# DC075B_USB.net
KiCad netlist of a schematic drawn in Altium Designer
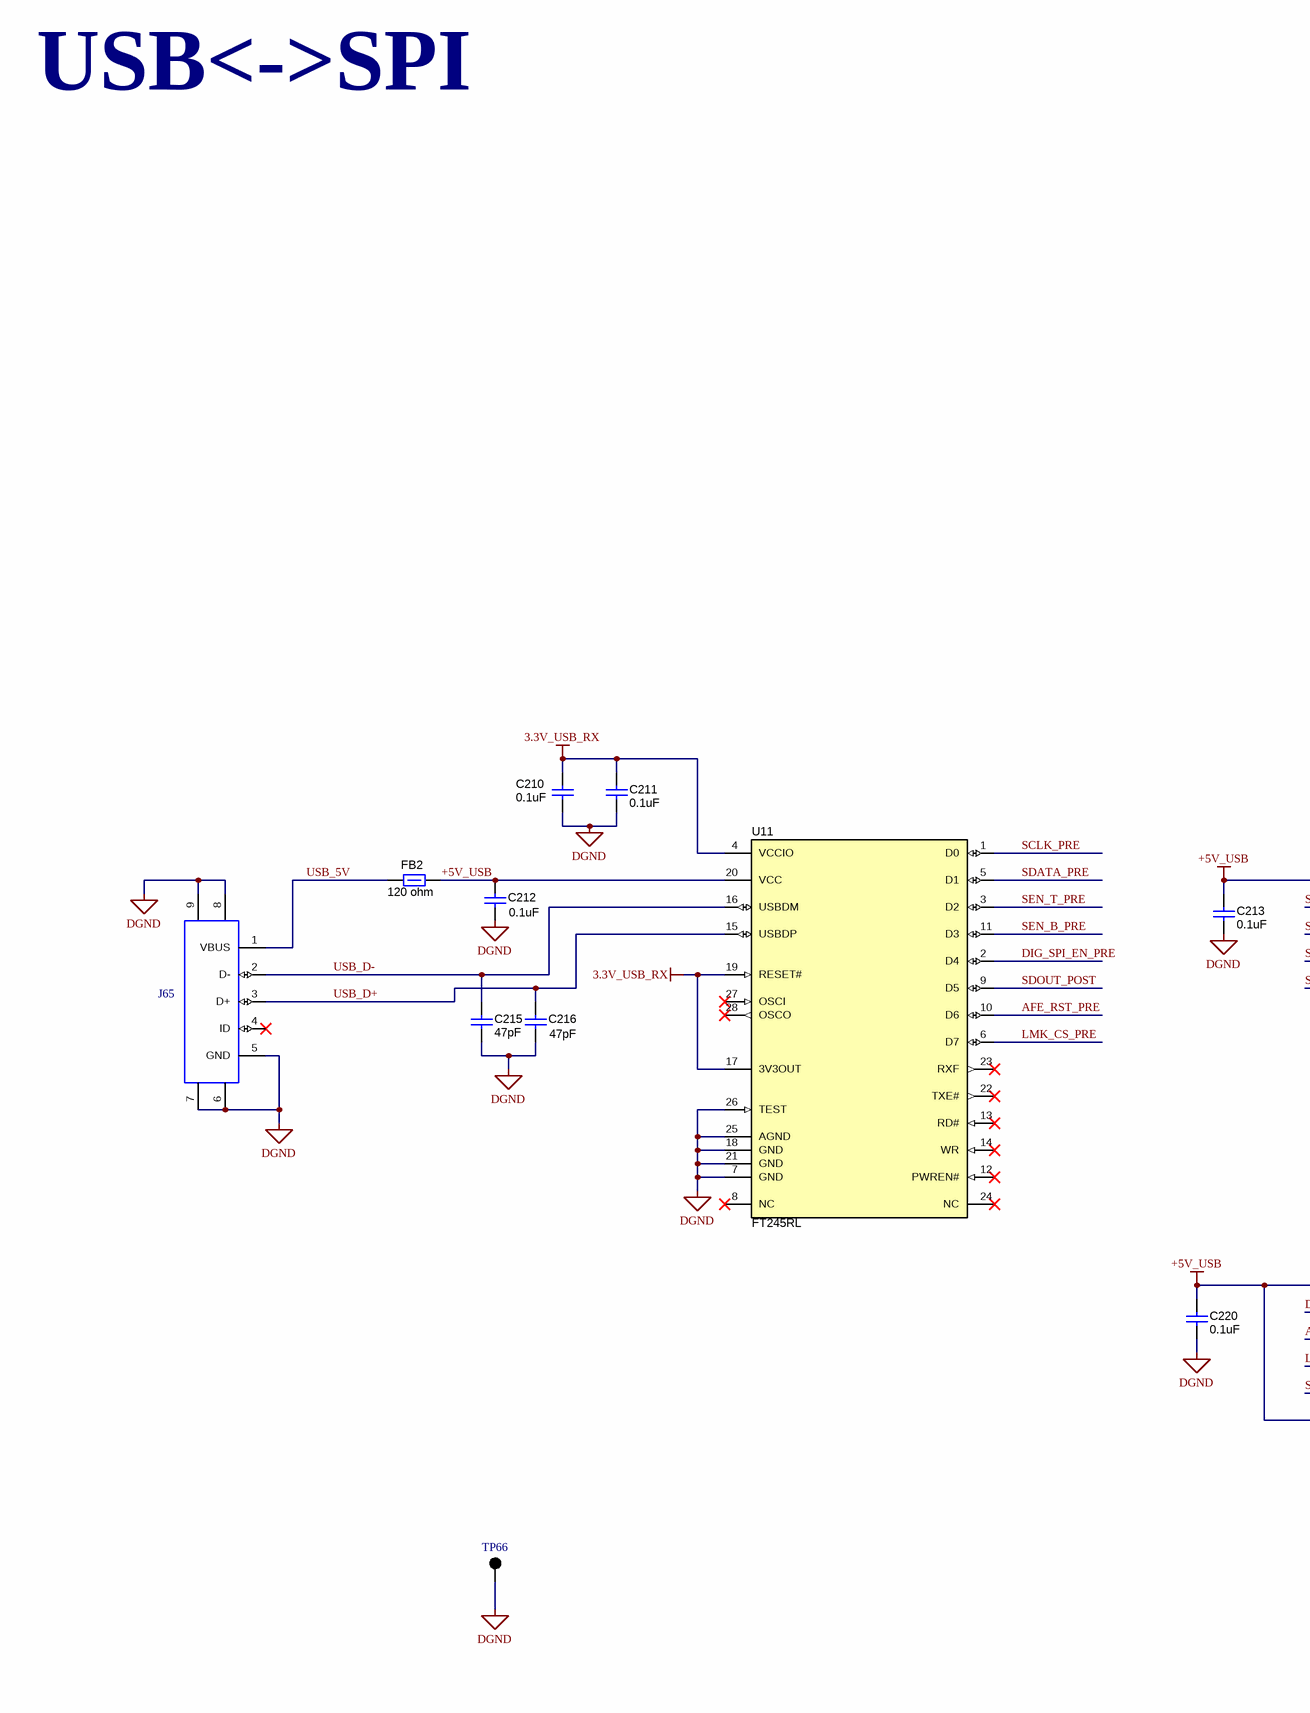
[diagram p0: DC075B_USB.SchDoc, left]
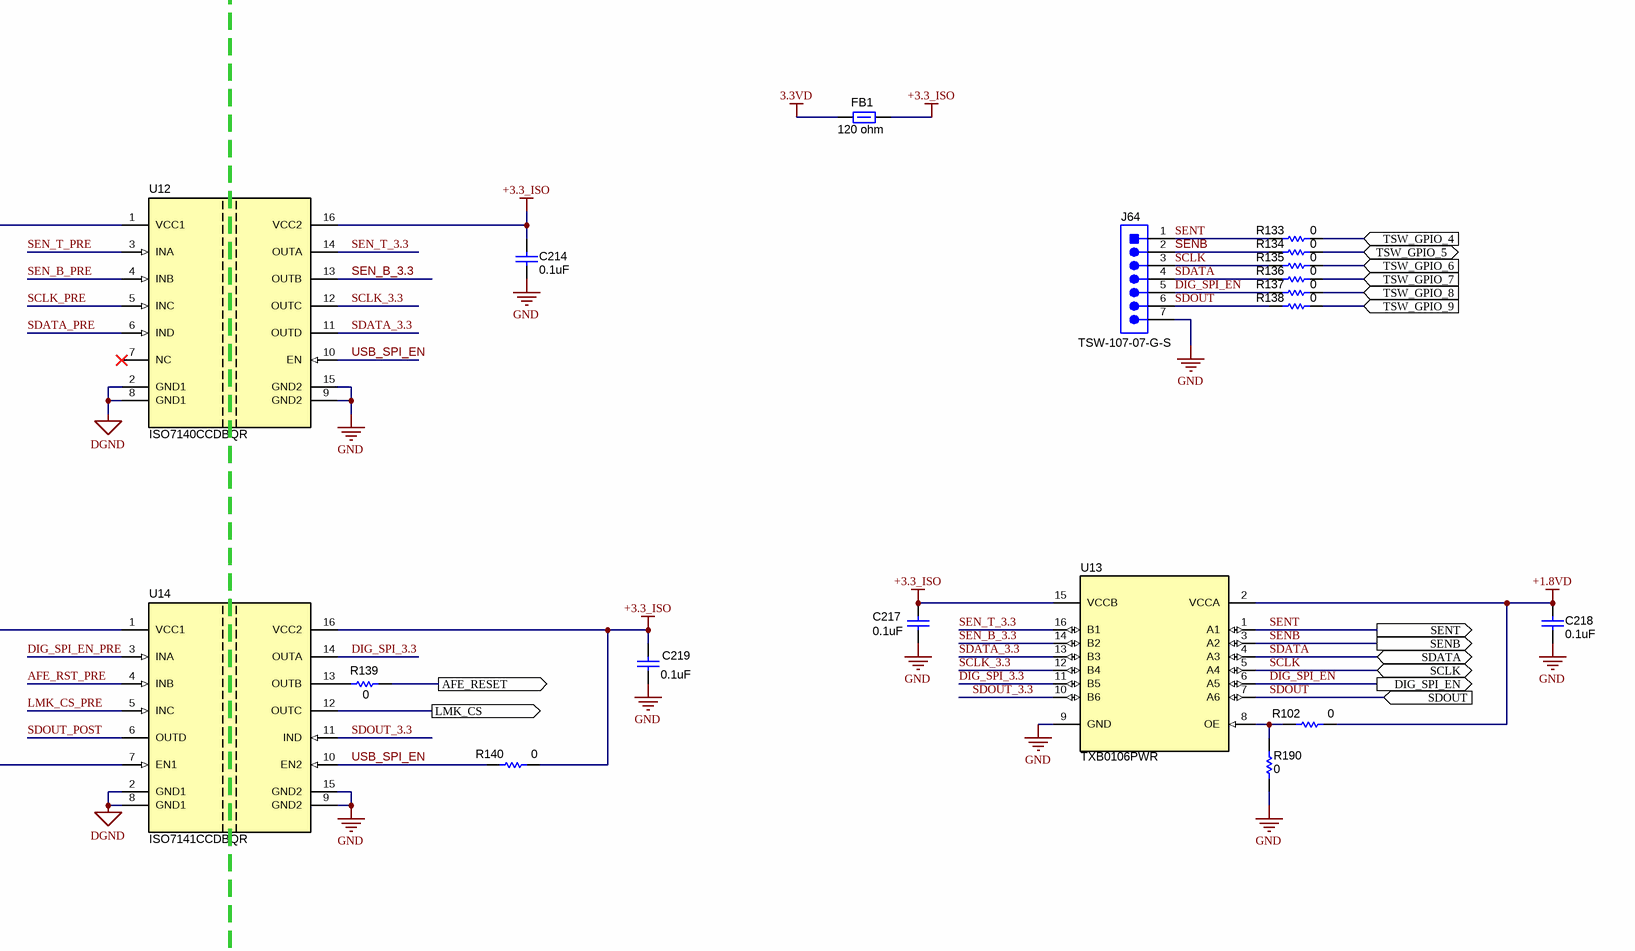
[diagram p1: DC075B_USB.SchDoc, right]

(export (version "E")
  (design (tool "Eeschema 10.0.6"))
  (components
    (comp (ref "C210")
      (value "0.1uF")
      (footprint "0402")
      (description "CAP, CERM, 0.1 uF, 16 V, +/- 10%, X7R, 0402")
      (fields
        (field (name "PARTNUMBER") "GRM155R71C104KA88D")
        (field (name "MANUFACTURER") "MuRata")
        (field (name "PUBLISHER") "Texas Instruments")
      )
      (libsource (lib "Altium Vault - TI") (part "Capacitor"))
    )
    (comp (ref "C211")
      (value "0.1uF")
      (footprint "0402")
      (description "CAP, CERM, 0.1 uF, 16 V, +/- 10%, X7R, 0402")
      (fields
        (field (name "PARTNUMBER") "GRM155R71C104KA88D")
        (field (name "MANUFACTURER") "MuRata")
        (field (name "PUBLISHER") "Texas Instruments")
      )
      (libsource (lib "Altium Vault - TI") (part "Capacitor"))
    )
    (comp (ref "C212")
      (value "0.1uF")
      (footprint "0402")
      (description "CAP, CERM, 0.1 uF, 16 V, +/- 10%, X7R, 0402")
      (fields
        (field (name "PARTNUMBER") "GRM155R71C104KA88D")
        (field (name "MANUFACTURER") "MuRata")
        (field (name "PUBLISHER") "Texas Instruments")
      )
      (libsource (lib "Altium Vault - TI") (part "Capacitor"))
    )
    (comp (ref "C213")
      (value "0.1uF")
      (footprint "0402")
      (description "CAP, CERM, 0.1 uF, 16 V, +/- 10%, X7R, 0402")
      (fields
        (field (name "PARTNUMBER") "GRM155R71C104KA88D")
        (field (name "MANUFACTURER") "MuRata")
        (field (name "PUBLISHER") "Texas Instruments")
      )
      (libsource (lib "Altium Vault - TI") (part "Capacitor"))
    )
    (comp (ref "C214")
      (value "0.1uF")
      (footprint "0402")
      (description "CAP, CERM, 0.1 uF, 16 V, +/- 10%, X7R, 0402")
      (fields
        (field (name "PARTNUMBER") "GRM155R71C104KA88D")
        (field (name "MANUFACTURER") "MuRata")
        (field (name "PUBLISHER") "Texas Instruments")
      )
      (libsource (lib "Altium Vault - TI") (part "Capacitor"))
    )
    (comp (ref "C215")
      (value "47pF")
      (footprint "0402")
      (description "CAP, CERM, 47 pF, 50 V, +/- 1%, C0G/NP0, 0402")
      (fields
        (field (name "PARTNUMBER") "GRM1555C1H470FA01D")
        (field (name "MANUFACTURER") "MuRata")
        (field (name "PUBLISHER") "Texas Instruments")
      )
      (libsource (lib "Altium Vault - TI") (part "Capacitor"))
    )
    (comp (ref "C216")
      (value "47pF")
      (footprint "0402")
      (description "CAP, CERM, 47 pF, 50 V, +/- 1%, C0G/NP0, 0402")
      (fields
        (field (name "PARTNUMBER") "GRM1555C1H470FA01D")
        (field (name "MANUFACTURER") "MuRata")
        (field (name "PUBLISHER") "Texas Instruments")
      )
      (libsource (lib "Altium Vault - TI") (part "Capacitor"))
    )
    (comp (ref "C217")
      (value "0.1uF")
      (footprint "0402")
      (description "CAP, CERM, 0.1 uF, 16 V, +/- 10%, X7R, 0402")
      (fields
        (field (name "PARTNUMBER") "GRM155R71C104KA88D")
        (field (name "MANUFACTURER") "MuRata")
        (field (name "PUBLISHER") "Texas Instruments")
      )
      (libsource (lib "Altium Vault - TI") (part "Capacitor"))
    )
    (comp (ref "C218")
      (value "0.1uF")
      (footprint "0402")
      (description "CAP, CERM, 0.1 uF, 16 V, +/- 10%, X7R, 0402")
      (fields
        (field (name "PARTNUMBER") "GRM155R71C104KA88D")
        (field (name "MANUFACTURER") "MuRata")
        (field (name "PUBLISHER") "Texas Instruments")
      )
      (libsource (lib "Altium Vault - TI") (part "Capacitor"))
    )
    (comp (ref "C219")
      (value "0.1uF")
      (footprint "0402")
      (description "CAP, CERM, 0.1 uF, 16 V, +/- 10%, X7R, 0402")
      (fields
        (field (name "PARTNUMBER") "GRM155R71C104KA88D")
        (field (name "MANUFACTURER") "MuRata")
        (field (name "PUBLISHER") "Texas Instruments")
      )
      (libsource (lib "Altium Vault - TI") (part "Capacitor"))
    )
    (comp (ref "C220")
      (value "0.1uF")
      (footprint "0402")
      (description "CAP, CERM, 0.1 uF, 16 V, +/- 10%, X7R, 0402")
      (fields
        (field (name "PARTNUMBER") "GRM155R71C104KA88D")
        (field (name "MANUFACTURER") "MuRata")
        (field (name "PUBLISHER") "Texas Instruments")
      )
      (libsource (lib "Altium Vault - TI") (part "Capacitor"))
    )
    (comp (ref "FB1")
      (value "120 ohm")
      (footprint "0805")
      (description "Ferrite Bead, 120 ohm @ 100 MHz, 0.8 A, 0805")
      (fields
        (field (name "MANUFACTURER") "MuRata")
        (field (name "PARTNUMBER") "BLM21AG121SN1D")
        (field (name "PUBLISHER") "Texas Instruments")
      )
      (libsource (lib "Altium Vault - TI") (part "Ferrite_Bead"))
    )
    (comp (ref "FB2")
      (value "120 ohm")
      (footprint "0805")
      (description "Ferrite Bead, 120 ohm @ 100 MHz, 0.8 A, 0805")
      (fields
        (field (name "MANUFACTURER") "MuRata")
        (field (name "PARTNUMBER") "BLM21AG121SN1D")
        (field (name "PUBLISHER") "Texas Instruments")
      )
      (libsource (lib "Altium Vault - TI") (part "Ferrite_Bead"))
    )
    (comp (ref "J64")
      (value "TSW-107-07-G-S")
      (footprint "TSW-107-07-G-S")
      (description "Header, 100mil, 7x1, Gold, TH")
      (fields (field (name "MANUFACTURER") "Samtec") (field (name "PUBLISHER") "Texas Instruments"))
      (libsource (lib "Altium Vault - TI") (part "Header_7x1"))
    )
    (comp (ref "J65")
      (value "67803-8020")
      (footprint "Molex_67803-8020")
      (description "Connector, Receptacle, USB - mini AB, R/A, SMD")
      (fields (field (name "MANUFACTURER") "Molex") (field (name "PUBLISHER") "Texas Instruments"))
      (libsource (lib "Altium Vault - TI") (part "CONN_USB_MINI-AB_4Shld"))
    )
    (comp (ref "R102")
      (value "0")
      (footprint "0402")
      (description "RES, 0, 5%, 0.063 W, AEC-Q200 Grade 0, 0402")
      (fields (field (name "MANUFACTURER") "Vishay-Dale") (field (name "PARTNUMBER") "CRCW04020000Z0ED"))
      (libsource (lib "Altium Vault - TI") (part "Resistor"))
    )
    (comp (ref "R133")
      (value "0")
      (footprint "0402")
      (description "RES, 0, 5%, 0.063 W, AEC-Q200 Grade 0, 0402")
      (fields (field (name "MANUFACTURER") "Vishay-Dale") (field (name "PARTNUMBER") "CRCW04020000Z0ED"))
      (libsource (lib "Altium Vault - TI") (part "Resistor"))
    )
    (comp (ref "R134")
      (value "0")
      (footprint "0402")
      (description "RES, 0, 5%, 0.063 W, AEC-Q200 Grade 0, 0402")
      (fields (field (name "MANUFACTURER") "Vishay-Dale") (field (name "PARTNUMBER") "CRCW04020000Z0ED"))
      (libsource (lib "Altium Vault - TI") (part "Resistor"))
    )
    (comp (ref "R135")
      (value "0")
      (footprint "0402")
      (description "RES, 0, 5%, 0.063 W, AEC-Q200 Grade 0, 0402")
      (fields (field (name "MANUFACTURER") "Vishay-Dale") (field (name "PARTNUMBER") "CRCW04020000Z0ED"))
      (libsource (lib "Altium Vault - TI") (part "Resistor"))
    )
    (comp (ref "R136")
      (value "0")
      (footprint "0402")
      (description "RES, 0, 5%, 0.063 W, AEC-Q200 Grade 0, 0402")
      (fields (field (name "MANUFACTURER") "Vishay-Dale") (field (name "PARTNUMBER") "CRCW04020000Z0ED"))
      (libsource (lib "Altium Vault - TI") (part "Resistor"))
    )
    (comp (ref "R137")
      (value "0")
      (footprint "0402")
      (description "RES, 0, 5%, 0.063 W, AEC-Q200 Grade 0, 0402")
      (fields (field (name "MANUFACTURER") "Vishay-Dale") (field (name "PARTNUMBER") "CRCW04020000Z0ED"))
      (libsource (lib "Altium Vault - TI") (part "Resistor"))
    )
    (comp (ref "R138")
      (value "0")
      (footprint "0402")
      (description "RES, 0, 5%, 0.063 W, AEC-Q200 Grade 0, 0402")
      (fields (field (name "MANUFACTURER") "Vishay-Dale") (field (name "PARTNUMBER") "CRCW04020000Z0ED"))
      (libsource (lib "Altium Vault - TI") (part "Resistor"))
    )
    (comp (ref "R139")
      (value "0")
      (footprint "0402")
      (description "RES, 0, 5%, 0.063 W, AEC-Q200 Grade 0, 0402")
      (fields (field (name "MANUFACTURER") "Vishay-Dale") (field (name "PARTNUMBER") "CRCW04020000Z0ED"))
      (libsource (lib "Altium Vault - TI") (part "Resistor"))
    )
    (comp (ref "R140")
      (value "0")
      (footprint "0402")
      (description "RES, 0, 5%, 0.063 W, AEC-Q200 Grade 0, 0402")
      (fields (field (name "MANUFACTURER") "Vishay-Dale") (field (name "PARTNUMBER") "CRCW04020000Z0ED"))
      (libsource (lib "Altium Vault - TI") (part "Resistor"))
    )
    (comp (ref "R190")
      (value "0")
      (footprint "0402")
      (description "RES, 0, 5%, 0.063 W, AEC-Q200 Grade 0, 0402")
      (fields (field (name "MANUFACTURER") "Vishay-Dale") (field (name "PARTNUMBER") "CRCW04020000Z0ED"))
      (libsource (lib "Altium Vault - TI") (part "Resistor"))
    )
    (comp (ref "TP66")
      (value "5001")
      (footprint "Keystone5001")
      (description "Test Point, Miniature, Black, TH")
      (fields (field (name "MANUFACTURER") "Keystone") (field (name "PUBLISHER") "Texas Instruments"))
      (libsource (lib "Altium Vault - TI") (part "5001"))
    )
    (comp (ref "U11")
      (value "FT245RL")
      (footprint "SSOP28_N")
      (description "USB FIFO IC, 28SSOP")
      (fields (field (name "MANUFACTURER") "FTDI") (field (name "PUBLISHER") "Texas Instruments"))
      (libsource (lib "Altium Vault - TI") (part "FT245RL"))
    )
    (comp (ref "U12")
      (value "ISO7140CCDBQR")
      (footprint "DBQ0016A_N")
      (fields
        (field (name "ALTERNATE PARTNUMBER") "ISO7140CCDBQ")
        (field (name "MANUFACTURER") "Texas Instruments")
        (field (name "PUBLISHER") "Texas Instruments")
      )
      (libsource (lib "Altium Vault - TI") (part "ISO7140"))
    )
    (comp (ref "U13")
      (value "TXB0106PWR")
      (footprint "PW0016A_N")
      (fields
        (field (name "MANUFACTURER") "Texas Instruments")
        (field (name "PUBLISHER") "Texas Instruments")
      )
      (libsource (lib "Altium Vault - TI") (part "TXB0106PW"))
    )
    (comp (ref "U14")
      (value "ISO7141CCDBQR")
      (footprint "DBQ0016A_N")
      (fields
        (field (name "ALTERNATE PARTNUMBER") "ISO7141CCDBQ")
        (field (name "MANUFACTURER") "Texas Instruments")
        (field (name "PUBLISHER") "Texas Instruments")
      )
      (libsource (lib "Altium Vault - TI") (part "ISO7141"))
    )
  )
  (nets
    (net (code "1") (name "+1.8VD") (class "Default")
      (node (ref "C218") (pin "2") (pinfunction "2_2") (pintype "passive"))
      (node (ref "R102") (pin "1") (pinfunction "1_1") (pintype "passive"))
      (node (ref "U13") (pin "2") (pinfunction "VCCA_2") (pintype "power_in"))
    )
    (net (code "2") (name "+3.3_ISO") (class "Default")
      (node (ref "C214") (pin "2") (pinfunction "2_2") (pintype "passive"))
      (node (ref "C217") (pin "2") (pinfunction "2_2") (pintype "passive"))
      (node (ref "C219") (pin "2") (pinfunction "2_2") (pintype "passive"))
      (node (ref "FB1") (pin "1") (pinfunction "1_1") (pintype "passive"))
      (node (ref "R140") (pin "1") (pinfunction "1_1") (pintype "passive"))
      (node (ref "U12") (pin "16") (pinfunction "VCC2_16") (pintype "power_in"))
      (node (ref "U13") (pin "15") (pinfunction "VCCB_15") (pintype "power_in"))
      (node (ref "U14") (pin "16") (pinfunction "VCC2_16") (pintype "power_in"))
    )
    (net (code "3") (name "+5V_USB") (class "Default")
      (node (ref "C212") (pin "1") (pinfunction "1_1") (pintype "passive"))
      (node (ref "C213") (pin "1") (pinfunction "1_1") (pintype "passive"))
      (node (ref "C220") (pin "1") (pinfunction "1_1") (pintype "passive"))
      (node (ref "FB2") (pin "1") (pinfunction "1_1") (pintype "passive"))
      (node (ref "U11") (pin "20") (pinfunction "VCC_20") (pintype "power_in"))
      (node (ref "U12") (pin "1") (pinfunction "VCC1_1") (pintype "power_in"))
      (node (ref "U14") (pin "1") (pinfunction "VCC1_1") (pintype "power_in"))
      (node (ref "U14") (pin "7") (pinfunction "EN1_7") (pintype "input"))
    )
    (net (code "4") (name "/AFE_RESET") (class "Default")
      (node (ref "R139") (pin "1") (pinfunction "1_1") (pintype "passive"))
    )
    (net (code "5") (name "/AFE_RST_PRE") (class "Default")
      (node (ref "U11") (pin "10") (pinfunction "D6_10") (pintype "bidirectional"))
      (node (ref "U14") (pin "4") (pinfunction "INB_4") (pintype "input"))
    )
    (net (code "6") (name "/DIG_SPI_3.3") (class "Default")
      (node (ref "U13") (pin "11") (pinfunction "B5_11") (pintype "bidirectional"))
      (node (ref "U14") (pin "14") (pinfunction "OUTA_14") (pintype "tri_state"))
    )
    (net (code "7") (name "/DIG_SPI_EN") (class "Default")
      (node (ref "J64") (pin "5") (pinfunction "5_5") (pintype "passive"))
      (node (ref "R137") (pin "2") (pinfunction "2_2") (pintype "passive"))
      (node (ref "U13") (pin "6") (pinfunction "A5_6") (pintype "bidirectional"))
    )
    (net (code "8") (name "/DIG_SPI_EN_PRE") (class "Default")
      (node (ref "U11") (pin "2") (pinfunction "D4_2") (pintype "bidirectional"))
      (node (ref "U14") (pin "3") (pinfunction "INA_3") (pintype "input"))
    )
    (net (code "9") (name "/LMK_CS") (class "Default")
      (node (ref "U14") (pin "12") (pinfunction "OUTC_12") (pintype "tri_state"))
    )
    (net (code "10") (name "/LMK_CS_PRE") (class "Default")
      (node (ref "U11") (pin "6") (pinfunction "D7_6") (pintype "bidirectional"))
      (node (ref "U14") (pin "5") (pinfunction "INC_5") (pintype "input"))
    )
    (net (code "11") (name "/SCLK") (class "Default")
      (node (ref "J64") (pin "3") (pinfunction "3_3") (pintype "passive"))
      (node (ref "R135") (pin "2") (pinfunction "2_2") (pintype "passive"))
      (node (ref "U13") (pin "5") (pinfunction "A4_5") (pintype "bidirectional"))
    )
    (net (code "12") (name "/SCLK_3.3") (class "Default")
      (node (ref "U12") (pin "12") (pinfunction "OUTC_12") (pintype "tri_state"))
      (node (ref "U13") (pin "12") (pinfunction "B4_12") (pintype "bidirectional"))
    )
    (net (code "13") (name "/SCLK_PRE") (class "Default")
      (node (ref "U11") (pin "1") (pinfunction "D0_1") (pintype "bidirectional"))
      (node (ref "U12") (pin "5") (pinfunction "INC_5") (pintype "input"))
    )
    (net (code "14") (name "/SDATA") (class "Default")
      (node (ref "J64") (pin "4") (pinfunction "4_4") (pintype "passive"))
      (node (ref "R136") (pin "2") (pinfunction "2_2") (pintype "passive"))
      (node (ref "U13") (pin "4") (pinfunction "A3_4") (pintype "bidirectional"))
    )
    (net (code "15") (name "/SDATA_3.3") (class "Default")
      (node (ref "U12") (pin "11") (pinfunction "OUTD_11") (pintype "tri_state"))
      (node (ref "U13") (pin "13") (pinfunction "B3_13") (pintype "bidirectional"))
    )
    (net (code "16") (name "/SDATA_PRE") (class "Default")
      (node (ref "U11") (pin "5") (pinfunction "D1_5") (pintype "bidirectional"))
      (node (ref "U12") (pin "6") (pinfunction "IND_6") (pintype "input"))
    )
    (net (code "17") (name "/SDOUT") (class "Default")
      (node (ref "J64") (pin "6") (pinfunction "6_6") (pintype "passive"))
      (node (ref "R138") (pin "2") (pinfunction "2_2") (pintype "passive"))
      (node (ref "U13") (pin "7") (pinfunction "A6_7") (pintype "bidirectional"))
    )
    (net (code "18") (name "/SDOUT_3.3") (class "Default")
      (node (ref "U13") (pin "10") (pinfunction "B6_10") (pintype "bidirectional"))
      (node (ref "U14") (pin "11") (pinfunction "IND_11") (pintype "input"))
    )
    (net (code "19") (name "/SDOUT_POST") (class "Default")
      (node (ref "U11") (pin "9") (pinfunction "D5_9") (pintype "bidirectional"))
      (node (ref "U14") (pin "6") (pinfunction "OUTD_6") (pintype "tri_state"))
    )
    (net (code "20") (name "/SENB") (class "Default")
      (node (ref "J64") (pin "2") (pinfunction "2_2") (pintype "passive"))
      (node (ref "R134") (pin "2") (pinfunction "2_2") (pintype "passive"))
      (node (ref "U13") (pin "3") (pinfunction "A2_3") (pintype "bidirectional"))
    )
    (net (code "21") (name "/SENT") (class "Default")
      (node (ref "J64") (pin "1") (pinfunction "1_1") (pintype "passive"))
      (node (ref "R133") (pin "2") (pinfunction "2_2") (pintype "passive"))
      (node (ref "U13") (pin "1") (pinfunction "A1_1") (pintype "bidirectional"))
    )
    (net (code "22") (name "/SEN_B_3.3") (class "Default")
      (node (ref "U12") (pin "13") (pinfunction "OUTB_13") (pintype "tri_state"))
      (node (ref "U13") (pin "14") (pinfunction "B2_14") (pintype "bidirectional"))
    )
    (net (code "23") (name "/SEN_B_PRE") (class "Default")
      (node (ref "U11") (pin "11") (pinfunction "D3_11") (pintype "bidirectional"))
      (node (ref "U12") (pin "4") (pinfunction "INB_4") (pintype "input"))
    )
    (net (code "24") (name "/SEN_T_3.3") (class "Default")
      (node (ref "U12") (pin "14") (pinfunction "OUTA_14") (pintype "tri_state"))
      (node (ref "U13") (pin "16") (pinfunction "B1_16") (pintype "bidirectional"))
    )
    (net (code "25") (name "/SEN_T_PRE") (class "Default")
      (node (ref "U11") (pin "3") (pinfunction "D2_3") (pintype "bidirectional"))
      (node (ref "U12") (pin "3") (pinfunction "INA_3") (pintype "input"))
    )
    (net (code "26") (name "/TSW_GPIO_4") (class "Default")
      (node (ref "R133") (pin "1") (pinfunction "1_1") (pintype "passive"))
    )
    (net (code "27") (name "/TSW_GPIO_5") (class "Default")
      (node (ref "R134") (pin "1") (pinfunction "1_1") (pintype "passive"))
    )
    (net (code "28") (name "/TSW_GPIO_6") (class "Default")
      (node (ref "R135") (pin "1") (pinfunction "1_1") (pintype "passive"))
    )
    (net (code "29") (name "/TSW_GPIO_7") (class "Default")
      (node (ref "R136") (pin "1") (pinfunction "1_1") (pintype "passive"))
    )
    (net (code "30") (name "/TSW_GPIO_8") (class "Default")
      (node (ref "R137") (pin "1") (pinfunction "1_1") (pintype "passive"))
    )
    (net (code "31") (name "/TSW_GPIO_9") (class "Default")
      (node (ref "R138") (pin "1") (pinfunction "1_1") (pintype "passive"))
    )
    (net (code "32") (name "/USB_5V") (class "Default")
      (node (ref "FB2") (pin "2") (pinfunction "2_2") (pintype "passive"))
      (node (ref "J65") (pin "1") (pinfunction "VBUS_1") (pintype "passive"))
    )
    (net (code "33") (name "/USB_D+") (class "Default")
      (node (ref "C216") (pin "1") (pinfunction "1_1") (pintype "passive"))
      (node (ref "J65") (pin "3") (pinfunction "D+_3") (pintype "bidirectional"))
      (node (ref "U11") (pin "15") (pinfunction "USBDP_15") (pintype "bidirectional"))
    )
    (net (code "34") (name "/USB_D-") (class "Default")
      (node (ref "C215") (pin "1") (pinfunction "1_1") (pintype "passive"))
      (node (ref "J65") (pin "2") (pinfunction "D-_2") (pintype "bidirectional"))
      (node (ref "U11") (pin "16") (pinfunction "USBDM_16") (pintype "bidirectional"))
    )
    (net (code "35") (name "/USB_SPI_EN") (class "Default")
      (node (ref "R140") (pin "2") (pinfunction "2_2") (pintype "passive"))
      (node (ref "U12") (pin "10") (pinfunction "EN_10") (pintype "input"))
      (node (ref "U14") (pin "10") (pinfunction "EN2_10") (pintype "input"))
    )
    (net (code "36") (name "3.3VD") (class "Default")
      (node (ref "FB1") (pin "2") (pinfunction "2_2") (pintype "passive"))
    )
    (net (code "37") (name "3.3V_USB_RX") (class "Default")
      (node (ref "C210") (pin "2") (pinfunction "2_2") (pintype "passive"))
      (node (ref "C211") (pin "2") (pinfunction "2_2") (pintype "passive"))
      (node (ref "U11") (pin "17") (pinfunction "3V3OUT_17") (pintype "power_in"))
      (node (ref "U11") (pin "19") (pinfunction "RESET#_19") (pintype "input"))
      (node (ref "U11") (pin "4") (pinfunction "VCCIO_4") (pintype "power_in"))
    )
    (net (code "38") (name "DGND") (class "Default")
      (node (ref "C210") (pin "1") (pinfunction "1_1") (pintype "passive"))
      (node (ref "C211") (pin "1") (pinfunction "1_1") (pintype "passive"))
      (node (ref "C212") (pin "2") (pinfunction "2_2") (pintype "passive"))
      (node (ref "C213") (pin "2") (pinfunction "2_2") (pintype "passive"))
      (node (ref "C215") (pin "2") (pinfunction "2_2") (pintype "passive"))
      (node (ref "C216") (pin "2") (pinfunction "2_2") (pintype "passive"))
      (node (ref "C220") (pin "2") (pinfunction "2_2") (pintype "passive"))
      (node (ref "J65") (pin "5") (pinfunction "GND_5") (pintype "passive"))
      (node (ref "J65") (pin "6") (pinfunction "6_6") (pintype "passive"))
      (node (ref "J65") (pin "7") (pinfunction "7_7") (pintype "passive"))
      (node (ref "J65") (pin "8") (pinfunction "8_8") (pintype "power_in"))
      (node (ref "J65") (pin "9") (pinfunction "9_9") (pintype "power_in"))
      (node (ref "TP66") (pin "1") (pintype "passive"))
      (node (ref "U11") (pin "18") (pinfunction "GND_18") (pintype "power_in"))
      (node (ref "U11") (pin "21") (pinfunction "GND_21") (pintype "power_in"))
      (node (ref "U11") (pin "25") (pinfunction "AGND_25") (pintype "power_in"))
      (node (ref "U11") (pin "26") (pinfunction "TEST_26") (pintype "input"))
      (node (ref "U11") (pin "7") (pinfunction "GND_7") (pintype "power_in"))
      (node (ref "U12") (pin "2") (pinfunction "GND1_2") (pintype "power_in"))
      (node (ref "U12") (pin "8") (pinfunction "GND1_8") (pintype "power_in"))
      (node (ref "U14") (pin "2") (pinfunction "GND1_2") (pintype "power_in"))
      (node (ref "U14") (pin "8") (pinfunction "GND1_8") (pintype "power_in"))
    )
    (net (code "39") (name "GND") (class "Default")
      (node (ref "C214") (pin "1") (pinfunction "1_1") (pintype "passive"))
      (node (ref "C217") (pin "1") (pinfunction "1_1") (pintype "passive"))
      (node (ref "C218") (pin "1") (pinfunction "1_1") (pintype "passive"))
      (node (ref "C219") (pin "1") (pinfunction "1_1") (pintype "passive"))
      (node (ref "J64") (pin "7") (pinfunction "7_7") (pintype "passive"))
      (node (ref "R190") (pin "2") (pinfunction "2_2") (pintype "passive"))
      (node (ref "U12") (pin "15") (pinfunction "GND2_15") (pintype "power_in"))
      (node (ref "U12") (pin "9") (pinfunction "GND2_9") (pintype "power_in"))
      (node (ref "U13") (pin "9") (pinfunction "GND_9") (pintype "power_in"))
      (node (ref "U14") (pin "15") (pinfunction "GND2_15") (pintype "power_in"))
      (node (ref "U14") (pin "9") (pinfunction "GND2_9") (pintype "power_in"))
    )
    (net (code "40") (name "Net-(U13-OE)") (class "Default")
      (node (ref "R102") (pin "2") (pinfunction "2_2") (pintype "passive"))
      (node (ref "R190") (pin "1") (pinfunction "1_1") (pintype "passive"))
      (node (ref "U13") (pin "8") (pinfunction "OE_8") (pintype "input"))
    )
    (net (code "41") (name "Net-(U14-OUTB)") (class "Default")
      (node (ref "R139") (pin "2") (pinfunction "2_2") (pintype "passive"))
      (node (ref "U14") (pin "13") (pinfunction "OUTB_13") (pintype "tri_state"))
    )
    (net (code "42") (name "unconnected-(J65-ID-Pad4)") (class "Default")
      (node (ref "J65") (pin "4") (pinfunction "ID_4") (pintype "bidirectional+no_connect"))
    )
    (net (code "43") (name "unconnected-(U11-NC-Pad8)") (class "Default")
      (node (ref "U11") (pin "8") (pinfunction "NC_8") (pintype "passive+no_connect"))
    )
    (net (code "44") (name "unconnected-(U11-NC-Pad24)") (class "Default")
      (node (ref "U11") (pin "24") (pinfunction "NC_24") (pintype "passive+no_connect"))
    )
    (net (code "45") (name "unconnected-(U11-OSCI-Pad27)") (class "Default")
      (node (ref "U11") (pin "27") (pinfunction "OSCI_27") (pintype "input+no_connect"))
    )
    (net (code "46") (name "unconnected-(U11-OSCO-Pad28)") (class "Default")
      (node (ref "U11") (pin "28") (pinfunction "OSCO_28") (pintype "output+no_connect"))
    )
    (net (code "47") (name "unconnected-(U11-PWREN#-Pad12)") (class "Default")
      (node (ref "U11") (pin "12") (pinfunction "PWREN#_12") (pintype "input+no_connect"))
    )
    (net (code "48") (name "unconnected-(U11-RD#-Pad13)") (class "Default")
      (node (ref "U11") (pin "13") (pinfunction "RD#_13") (pintype "input+no_connect"))
    )
    (net (code "49") (name "unconnected-(U11-RXF-Pad23)") (class "Default")
      (node (ref "U11") (pin "23") (pinfunction "RXF_23") (pintype "output+no_connect"))
    )
    (net (code "50") (name "unconnected-(U11-TXE#-Pad22)") (class "Default")
      (node (ref "U11") (pin "22") (pinfunction "TXE#_22") (pintype "output+no_connect"))
    )
    (net (code "51") (name "unconnected-(U11-WR-Pad14)") (class "Default")
      (node (ref "U11") (pin "14") (pinfunction "WR_14") (pintype "input+no_connect"))
    )
    (net (code "52") (name "unconnected-(U12-NC-Pad7)") (class "Default")
      (node (ref "U12") (pin "7") (pinfunction "NC_7") (pintype "passive+no_connect"))
    )
  )
)
